# circuit_r3.net
KiCad netlist of a schematic drawn in EAGLE
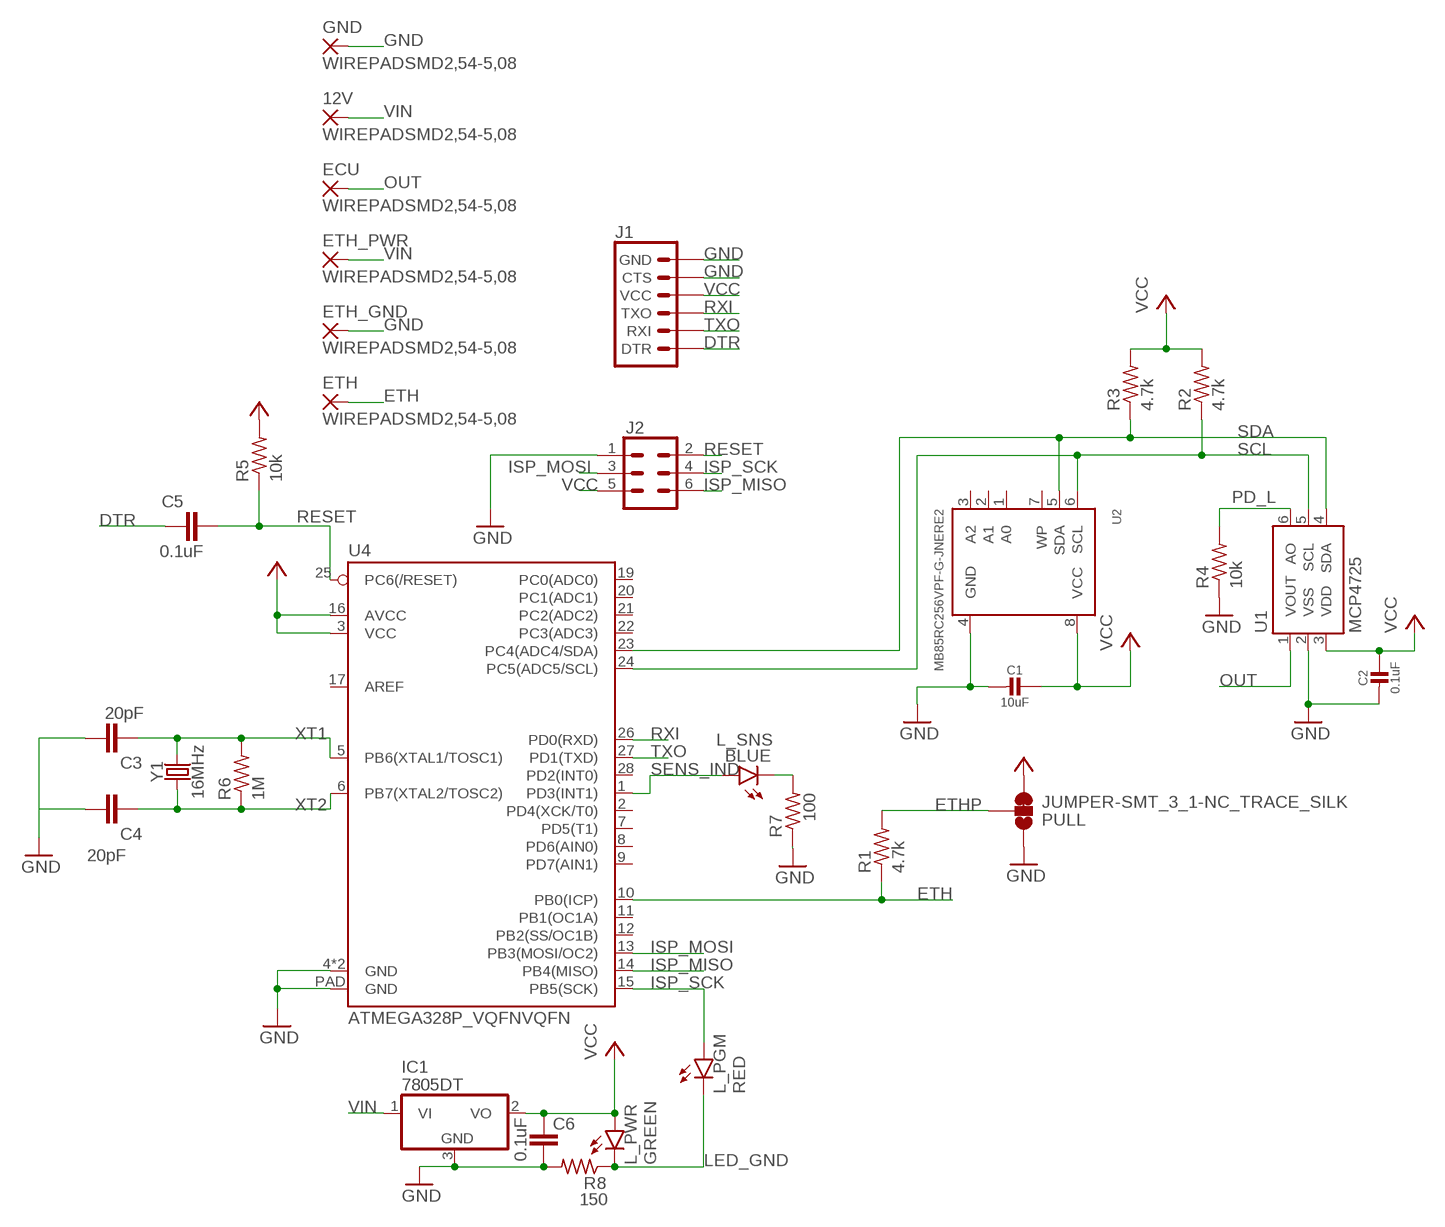
[diagram p0: schematic, sheet 1]

(export (version "E")
  (design (tool "Eeschema 10.0.6"))
  (components
    (comp (ref "12V")
      (value "WIREPADSMD2,54-5,08")
      (footprint "eagle-import:SMD2,54-5,08")
      (libsource (lib "eagle-import") (part "WIREPADSMD2,54-5,08"))
    )
    (comp (ref "C1")
      (value "10uF")
      (footprint "eagle-import:_0805")
      (libsource (lib "eagle-import") (part "CAP_CERAMIC_0805"))
    )
    (comp (ref "C2")
      (value "0.1uF")
      (footprint "eagle-import:_0603")
      (libsource (lib "eagle-import") (part "CAP_CERAMIC_0603"))
    )
    (comp (ref "C3")
      (value "20pF")
      (footprint "eagle-import:0603")
      (libsource (lib "eagle-import") (part "C"))
    )
    (comp (ref "C4")
      (value "20pF")
      (footprint "eagle-import:0603")
      (libsource (lib "eagle-import") (part "C"))
    )
    (comp (ref "C5")
      (value "0.1uF")
      (footprint "eagle-import:0603")
      (libsource (lib "eagle-import") (part "C"))
    )
    (comp (ref "C6")
      (value "0.1uF")
      (footprint "eagle-import:0603")
      (libsource (lib "eagle-import") (part "C"))
    )
    (comp (ref "ECU")
      (value "WIREPADSMD2,54-5,08")
      (footprint "eagle-import:SMD2,54-5,08")
      (libsource (lib "eagle-import") (part "WIREPADSMD2,54-5,08"))
    )
    (comp (ref "ETH")
      (value "WIREPADSMD2,54-5,08")
      (footprint "eagle-import:SMD2,54-5,08")
      (libsource (lib "eagle-import") (part "WIREPADSMD2,54-5,08"))
    )
    (comp (ref "ETH_GND")
      (value "WIREPADSMD2,54-5,08")
      (footprint "eagle-import:SMD2,54-5,08")
      (libsource (lib "eagle-import") (part "WIREPADSMD2,54-5,08"))
    )
    (comp (ref "ETH_PWR")
      (value "WIREPADSMD2,54-5,08")
      (footprint "eagle-import:SMD2,54-5,08")
      (libsource (lib "eagle-import") (part "WIREPADSMD2,54-5,08"))
    )
    (comp (ref "GND")
      (value "WIREPADSMD2,54-5,08")
      (footprint "eagle-import:SMD2,54-5,08")
      (libsource (lib "eagle-import") (part "WIREPADSMD2,54-5,08"))
    )
    (comp (ref "IC1")
      (value "7805DT")
      (footprint "eagle-import:TO252")
      (libsource (lib "eagle-import") (part "78DT05"))
    )
    (comp (ref "J1")
      (value "6_PIN_SERIAL_TARGETSILK")
      (footprint "eagle-import:6_PIN_SERIAL_TARGET_SIDE_W_SILK")
      (libsource (lib "eagle-import") (part "6_PIN_SERIAL_TARGETSILK"))
    )
    (comp (ref "J2")
      (value "CONN_03X22X3_SILK_MALE_PTH")
      (footprint "eagle-import:2X3")
      (libsource (lib "eagle-import") (part "CONN_03X22X3_SILK_MALE_PTH"))
    )
    (comp (ref "L_PGM")
      (value "RED")
      (footprint "eagle-import:LED-0603")
      (libsource (lib "eagle-import") (part "LED-RED0603"))
    )
    (comp (ref "L_PWR")
      (value "GREEN")
      (footprint "eagle-import:LED-0603")
      (libsource (lib "eagle-import") (part "LED-RED0603"))
    )
    (comp (ref "L_SNS")
      (value "BLUE")
      (footprint "eagle-import:LED-0603")
      (libsource (lib "eagle-import") (part "LED-RED0603"))
    )
    (comp (ref "PULL")
      (value "JUMPER-SMT_3_1-NC_TRACE_SILK")
      (footprint "eagle-import:SMT-JUMPER_3_1-NC_TRACE_SILK")
      (libsource (lib "eagle-import") (part "JUMPER-SMT_3_1-NC_TRACE_SILK"))
    )
    (comp (ref "R1")
      (value "4.7k")
      (footprint "eagle-import:R0603")
      (libsource (lib "eagle-import") (part "R-US_R0603"))
    )
    (comp (ref "R2")
      (value "4.7k")
      (footprint "eagle-import:R0603")
      (libsource (lib "eagle-import") (part "R-US_R0603"))
    )
    (comp (ref "R3")
      (value "4.7k")
      (footprint "eagle-import:R0603")
      (libsource (lib "eagle-import") (part "R-US_R0603"))
    )
    (comp (ref "R4")
      (value "10k")
      (footprint "eagle-import:R0603")
      (libsource (lib "eagle-import") (part "R-US_R0603"))
    )
    (comp (ref "R5")
      (value "10k")
      (footprint "eagle-import:R0603")
      (libsource (lib "eagle-import") (part "R-US_R0603"))
    )
    (comp (ref "R6")
      (value "1M")
      (footprint "eagle-import:R0603")
      (libsource (lib "eagle-import") (part "R-US_R0603"))
    )
    (comp (ref "R7")
      (value "100")
      (footprint "eagle-import:R0603")
      (libsource (lib "eagle-import") (part "R-US_R0603"))
    )
    (comp (ref "R8")
      (value "150")
      (footprint "eagle-import:R0603")
      (libsource (lib "eagle-import") (part "R-US_R0603"))
    )
    (comp (ref "U1")
      (value "MCP4725")
      (footprint "eagle-import:SOT23-6")
      (libsource (lib "eagle-import") (part "MCP4725SOT-23"))
    )
    (comp (ref "U2")
      (value "MB85RC256VPF-G-JNERE2")
      (footprint "eagle-import:SOIC8_208MIL")
      (libsource (lib "eagle-import") (part "FRAM_SOIC8_I2C"))
    )
    (comp (ref "U4")
      (value "ATMEGA328P_VQFNVQFN")
      (footprint "eagle-import:VQFN-28")
      (libsource (lib "eagle-import") (part "ATMEGA328P_VQFNVQFN"))
    )
    (comp (ref "Y1")
      (value "16MHz")
      (footprint "eagle-import:CRYSTAL-SMD-5X3.2-4PAD")
      (libsource (lib "eagle-import") (part "CRYSTAL-16MHZSMD-5X3.2"))
    )
  )
  (nets
    (net (code "1") (name "/DTR") (class "Default")
      (node (ref "C5") (pin "2") (pinfunction "2_2") (pintype "power_in"))
      (node (ref "J1") (pin "P$1") (pinfunction "DTR_P$1") (pintype "passive"))
    )
    (net (code "2") (name "/ETH") (class "Default")
      (node (ref "ETH") (pin "1") (pinfunction "P_1") (pintype "passive"))
      (node (ref "R1") (pin "1") (pinfunction "1_1") (pintype "passive"))
      (node (ref "U4") (pin "10") (pinfunction "PB0(ICP)_10") (pintype "bidirectional"))
    )
    (net (code "3") (name "/ETHP") (class "Default")
      (node (ref "PULL") (pin "2") (pinfunction "2_2") (pintype "passive"))
      (node (ref "R1") (pin "2") (pinfunction "2_2") (pintype "passive"))
    )
    (net (code "4") (name "/ISP_MISO") (class "Default")
      (node (ref "J2") (pin "6") (pinfunction "6_6") (pintype "bidirectional"))
      (node (ref "U4") (pin "14") (pinfunction "PB4(MISO)_14") (pintype "bidirectional"))
    )
    (net (code "5") (name "/ISP_MOSI") (class "Default")
      (node (ref "J2") (pin "3") (pinfunction "3_3") (pintype "bidirectional"))
      (node (ref "U4") (pin "13") (pinfunction "PB3(MOSI/OC2)_13") (pintype "bidirectional"))
    )
    (net (code "6") (name "/ISP_SCK") (class "Default")
      (node (ref "J2") (pin "4") (pinfunction "4_4") (pintype "bidirectional"))
      (node (ref "L_PGM") (pin "A") (pinfunction "A_A") (pintype "passive"))
      (node (ref "U4") (pin "15") (pinfunction "PB5(SCK)_15") (pintype "bidirectional"))
    )
    (net (code "7") (name "/LED_GND") (class "Default")
      (node (ref "L_PGM") (pin "C") (pinfunction "C_C") (pintype "passive"))
      (node (ref "L_PWR") (pin "C") (pinfunction "C_C") (pintype "passive"))
      (node (ref "R8") (pin "1") (pinfunction "1_1") (pintype "passive"))
    )
    (net (code "8") (name "/OUT") (class "Default")
      (node (ref "ECU") (pin "1") (pinfunction "P_1") (pintype "passive"))
      (node (ref "U1") (pin "1") (pinfunction "VOUT_1") (pintype "bidirectional"))
    )
    (net (code "9") (name "/PD_L") (class "Default")
      (node (ref "R4") (pin "2") (pinfunction "2_2") (pintype "passive"))
      (node (ref "U1") (pin "6") (pinfunction "AO_6") (pintype "bidirectional"))
    )
    (net (code "10") (name "/RESET") (class "Default")
      (node (ref "C5") (pin "1") (pinfunction "1_1") (pintype "power_in"))
      (node (ref "J2") (pin "2") (pinfunction "2_2") (pintype "bidirectional"))
      (node (ref "R5") (pin "1") (pinfunction "1_1") (pintype "passive"))
      (node (ref "U4") (pin "25") (pinfunction "PC6(/RESET)_25") (pintype "bidirectional"))
    )
    (net (code "11") (name "/RXI") (class "Default")
      (node (ref "J1") (pin "P$2") (pinfunction "TXO_P$2") (pintype "passive"))
      (node (ref "U4") (pin "26") (pinfunction "PD0(RXD)_26") (pintype "bidirectional"))
    )
    (net (code "12") (name "/SCL") (class "Default")
      (node (ref "R2") (pin "1") (pinfunction "1_1") (pintype "passive"))
      (node (ref "U1") (pin "5") (pinfunction "SCL_5") (pintype "bidirectional"))
      (node (ref "U2") (pin "6") (pinfunction "SCL_6") (pintype "input"))
      (node (ref "U4") (pin "24") (pinfunction "PC5(ADC5/SCL)_24") (pintype "bidirectional"))
    )
    (net (code "13") (name "/SDA") (class "Default")
      (node (ref "R3") (pin "1") (pinfunction "1_1") (pintype "passive"))
      (node (ref "U1") (pin "4") (pinfunction "SDA_4") (pintype "bidirectional"))
      (node (ref "U2") (pin "5") (pinfunction "SDA_5") (pintype "bidirectional"))
      (node (ref "U4") (pin "23") (pinfunction "PC4(ADC4/SDA)_23") (pintype "bidirectional"))
    )
    (net (code "14") (name "/SENS_IND") (class "Default")
      (node (ref "L_SNS") (pin "A") (pinfunction "A_A") (pintype "passive"))
      (node (ref "U4") (pin "1") (pinfunction "PD3(INT1)_1") (pintype "bidirectional"))
    )
    (net (code "15") (name "/TXO") (class "Default")
      (node (ref "J1") (pin "P$3") (pinfunction "RXI_P$3") (pintype "passive"))
      (node (ref "U4") (pin "27") (pinfunction "PD1(TXD)_27") (pintype "bidirectional"))
    )
    (net (code "16") (name "/VIN") (class "Default")
      (node (ref "12V") (pin "1") (pinfunction "P_1") (pintype "passive"))
      (node (ref "ETH_PWR") (pin "1") (pinfunction "P_1") (pintype "passive"))
      (node (ref "IC1") (pin "1") (pinfunction "VI_1") (pintype "input"))
    )
    (net (code "17") (name "/XT1") (class "Default")
      (node (ref "C3") (pin "2") (pinfunction "2_2") (pintype "power_in"))
      (node (ref "R6") (pin "2") (pinfunction "2_2") (pintype "passive"))
      (node (ref "U4") (pin "5") (pinfunction "PB6(XTAL1/TOSC1)_5") (pintype "bidirectional"))
      (node (ref "Y1") (pin "3") (pinfunction "2_3") (pintype "passive"))
    )
    (net (code "18") (name "/XT2") (class "Default")
      (node (ref "C4") (pin "2") (pinfunction "2_2") (pintype "power_in"))
      (node (ref "R6") (pin "1") (pinfunction "1_1") (pintype "passive"))
      (node (ref "U4") (pin "6") (pinfunction "PB7(XTAL2/TOSC2)_6") (pintype "bidirectional"))
      (node (ref "Y1") (pin "1") (pinfunction "1_1") (pintype "passive"))
    )
    (net (code "19") (name "GND") (class "Default")
      (node (ref "C1") (pin "2") (pinfunction "2_2") (pintype "passive"))
      (node (ref "C2") (pin "2") (pinfunction "2_2") (pintype "passive"))
      (node (ref "C3") (pin "1") (pinfunction "1_1") (pintype "power_in"))
      (node (ref "C4") (pin "1") (pinfunction "1_1") (pintype "power_in"))
      (node (ref "C6") (pin "1") (pinfunction "1_1") (pintype "power_in"))
      (node (ref "ETH_GND") (pin "1") (pinfunction "P_1") (pintype "passive"))
      (node (ref "GND") (pin "1") (pinfunction "P_1") (pintype "passive"))
      (node (ref "IC1") (pin "3") (pinfunction "GND_3") (pintype "passive"))
      (node (ref "J1") (pin "P$5") (pinfunction "CTS_P$5") (pintype "passive"))
      (node (ref "J1") (pin "P$6") (pinfunction "GND_P$6") (pintype "passive"))
      (node (ref "J2") (pin "1") (pinfunction "1_1") (pintype "bidirectional"))
      (node (ref "PULL") (pin "1") (pinfunction "1_1") (pintype "passive"))
      (node (ref "R4") (pin "1") (pinfunction "1_1") (pintype "passive"))
      (node (ref "R7") (pin "1") (pinfunction "1_1") (pintype "passive"))
      (node (ref "R8") (pin "2") (pinfunction "2_2") (pintype "passive"))
      (node (ref "U1") (pin "2") (pinfunction "VSS_2") (pintype "bidirectional"))
      (node (ref "U2") (pin "4") (pinfunction "GND_4") (pintype "power_in"))
      (node (ref "U4") (pin "18") (pinfunction "GND_18") (pintype "bidirectional"))
      (node (ref "U4") (pin "4") (pinfunction "GND_4") (pintype "bidirectional"))
      (node (ref "U4") (pin "PAD") (pinfunction "GND_PAD") (pintype "bidirectional"))
    )
    (net (code "20") (name "Net-(L_SNS-PadC)") (class "Default")
      (node (ref "L_SNS") (pin "C") (pinfunction "C_C") (pintype "passive"))
      (node (ref "R7") (pin "2") (pinfunction "2_2") (pintype "passive"))
    )
    (net (code "21") (name "VCC") (class "Default")
      (node (ref "C1") (pin "1") (pinfunction "1_1") (pintype "passive"))
      (node (ref "C2") (pin "1") (pinfunction "1_1") (pintype "passive"))
      (node (ref "C6") (pin "2") (pinfunction "2_2") (pintype "power_in"))
      (node (ref "IC1") (pin "2") (pinfunction "VO_2") (pintype "passive"))
      (node (ref "J1") (pin "P$4") (pinfunction "VCC_P$4") (pintype "passive"))
      (node (ref "J2") (pin "5") (pinfunction "5_5") (pintype "bidirectional"))
      (node (ref "L_PWR") (pin "A") (pinfunction "A_A") (pintype "passive"))
      (node (ref "PULL") (pin "3") (pinfunction "3_3") (pintype "passive"))
      (node (ref "R2") (pin "2") (pinfunction "2_2") (pintype "passive"))
      (node (ref "R3") (pin "2") (pinfunction "2_2") (pintype "passive"))
      (node (ref "R5") (pin "2") (pinfunction "2_2") (pintype "passive"))
      (node (ref "U1") (pin "3") (pinfunction "VDD_3") (pintype "bidirectional"))
      (node (ref "U2") (pin "8") (pinfunction "VCC_8") (pintype "power_in"))
      (node (ref "U4") (pin "16") (pinfunction "AVCC_16") (pintype "bidirectional"))
      (node (ref "U4") (pin "3") (pinfunction "VCC_3") (pintype "bidirectional"))
    )
    (net (code "22") (name "unconnected-(U2-A0-Pad1)") (class "Default")
      (node (ref "U2") (pin "1") (pinfunction "A0_1") (pintype "input"))
    )
    (net (code "23") (name "unconnected-(U2-A1-Pad2)") (class "Default")
      (node (ref "U2") (pin "2") (pinfunction "A1_2") (pintype "input"))
    )
    (net (code "24") (name "unconnected-(U2-A2-Pad3)") (class "Default")
      (node (ref "U2") (pin "3") (pinfunction "A2_3") (pintype "input"))
    )
    (net (code "25") (name "unconnected-(U2-WP-Pad7)") (class "Default")
      (node (ref "U2") (pin "7") (pinfunction "WP_7") (pintype "input"))
    )
    (net (code "26") (name "unconnected-(U4-AREF-Pad17)") (class "Default")
      (node (ref "U4") (pin "17") (pinfunction "AREF_17") (pintype "bidirectional"))
    )
    (net (code "27") (name "unconnected-(U4-PB1(OC1A)-Pad11)") (class "Default")
      (node (ref "U4") (pin "11") (pinfunction "PB1(OC1A)_11") (pintype "bidirectional"))
    )
    (net (code "28") (name "unconnected-(U4-PB2(SS{slash}OC1B)-Pad12)") (class "Default")
      (node (ref "U4") (pin "12") (pinfunction "PB2(SS/OC1B)_12") (pintype "bidirectional"))
    )
    (net (code "29") (name "unconnected-(U4-PC0(ADC0)-Pad19)") (class "Default")
      (node (ref "U4") (pin "19") (pinfunction "PC0(ADC0)_19") (pintype "bidirectional"))
    )
    (net (code "30") (name "unconnected-(U4-PC1(ADC1)-Pad20)") (class "Default")
      (node (ref "U4") (pin "20") (pinfunction "PC1(ADC1)_20") (pintype "bidirectional"))
    )
    (net (code "31") (name "unconnected-(U4-PC2(ADC2)-Pad21)") (class "Default")
      (node (ref "U4") (pin "21") (pinfunction "PC2(ADC2)_21") (pintype "bidirectional"))
    )
    (net (code "32") (name "unconnected-(U4-PC3(ADC3)-Pad22)") (class "Default")
      (node (ref "U4") (pin "22") (pinfunction "PC3(ADC3)_22") (pintype "bidirectional"))
    )
    (net (code "33") (name "unconnected-(U4-PD2(INT0)-Pad28)") (class "Default")
      (node (ref "U4") (pin "28") (pinfunction "PD2(INT0)_28") (pintype "bidirectional"))
    )
    (net (code "34") (name "unconnected-(U4-PD4(XCK{slash}T0)-Pad2)") (class "Default")
      (node (ref "U4") (pin "2") (pinfunction "PD4(XCK/T0)_2") (pintype "bidirectional"))
    )
    (net (code "35") (name "unconnected-(U4-PD5(T1)-Pad7)") (class "Default")
      (node (ref "U4") (pin "7") (pinfunction "PD5(T1)_7") (pintype "bidirectional"))
    )
    (net (code "36") (name "unconnected-(U4-PD6(AIN0)-Pad8)") (class "Default")
      (node (ref "U4") (pin "8") (pinfunction "PD6(AIN0)_8") (pintype "bidirectional"))
    )
    (net (code "37") (name "unconnected-(U4-PD7(AIN1)-Pad9)") (class "Default")
      (node (ref "U4") (pin "9") (pinfunction "PD7(AIN1)_9") (pintype "bidirectional"))
    )
  )
)
